# 3_3VBuckConverterSM.net
KiCad netlist of a schematic drawn in Altium Designer
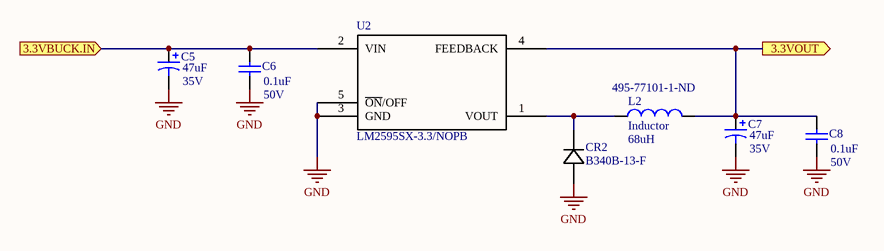
[diagram p0: 3.3VBuckConverterSM.SchDoc]

(export (version "E")
  (design (tool "Eeschema 10.0.6"))
  (components
    (comp (ref "C5")
      (value "47uF")
      (footprint "RB7.6-15")
      (description "Polarized Capacitor (Radial)")
      (fields
        (field (name "VOLTAGE RATING") "35V")
        (field (name "Comment") "Cap Pol1")
        (field (name "PUBLISHER") "Altium Limited")
      )
      (libsource (lib "Miscellaneous Devices") (part "Cap Pol1"))
    )
    (comp (ref "C6")
      (value "0.1uF")
      (footprint "RAD-0.3")
      (description "Capacitor")
      (fields
        (field (name "VOLTAGE RATING") "50V")
        (field (name "Comment") "Cap")
        (field (name "PUBLISHER") "Altium Limited")
      )
      (libsource (lib "Miscellaneous Devices") (part "Cap"))
    )
    (comp (ref "C7")
      (value "47uF")
      (footprint "RB7.6-15")
      (description "Polarized Capacitor (Radial)")
      (fields
        (field (name "VOLTAGE RATING") "35V")
        (field (name "Comment") "Cap Pol1")
        (field (name "PUBLISHER") "Altium Limited")
      )
      (libsource (lib "Miscellaneous Devices") (part "Cap Pol1"))
    )
    (comp (ref "C8")
      (value "0.1uF")
      (footprint "RAD-0.3")
      (description "Capacitor")
      (fields
        (field (name "VOLTAGE RATING") "50V")
        (field (name "Comment") "Cap")
        (field (name "PUBLISHER") "Altium Limited")
      )
      (libsource (lib "Miscellaneous Devices") (part "Cap"))
    )
    (comp (ref "CR2")
      (value "B340B-13-F")
      (footprint "B340A-13-F")
      (description "No Description Available")
      (fields (field (name "COPYRIGHT") "Copyright (C) 2022 Ultra Librarian. All rights reserved."))
      (libsource (lib "B340B-13-F") (part "B340B-13-F"))
    )
    (comp (ref "L2")
      (value "Inductor")
      (footprint "B82472P6683M000")
      (description "Ind Power Shielded Wirewound 68uH 20% 100KHz Ferrite 820mA Blister T/R")
      (fields
        (field (name "ALTIUM_VALUE") "68uH")
        (field (name "SUPPLIER PART NUMBER 1") "495-77101-1-ND")
        (field (name "MANUFACTURER") "TDK EPCOS")
        (field (name "MANUFACTURER PART NUMBER") "B82472P6683M000")
        (field (name "PUBLISHER") "Altium Limited")
      )
      (libsource (lib "Miscellaneous Devices") (part "Inductor"))
    )
    (comp (ref "U2")
      (value "LM2595SX-3.3/NOPB")
      (footprint "LM2595SX-3P3")
      (libsource (lib "Parts") (part "LM2595SX-3.3/NOPB"))
    )
  )
  (nets
    (net (code "1") (name "/3.3VBUCK.IN") (class "Default")
      (node (ref "C5") (pin "1") (pinfunction "1_1") (pintype "passive"))
      (node (ref "C6") (pin "2") (pinfunction "2_2") (pintype "passive"))
      (node (ref "U2") (pin "2") (pinfunction "VIN_2") (pintype "passive"))
    )
    (net (code "2") (name "/3.3VOUT") (class "Default")
      (node (ref "C7") (pin "1") (pinfunction "1_1") (pintype "passive"))
      (node (ref "C8") (pin "2") (pinfunction "2_2") (pintype "passive"))
      (node (ref "L2") (pin "2") (pinfunction "2_2") (pintype "passive"))
      (node (ref "U2") (pin "4") (pinfunction "FEEDBACK_4") (pintype "passive"))
    )
    (net (code "3") (name "GND") (class "Default")
      (node (ref "C5") (pin "2") (pinfunction "2_2") (pintype "passive"))
      (node (ref "C6") (pin "1") (pinfunction "1_1") (pintype "passive"))
      (node (ref "C7") (pin "2") (pinfunction "2_2") (pintype "passive"))
      (node (ref "C8") (pin "1") (pinfunction "1_1") (pintype "passive"))
      (node (ref "CR2") (pin "2") (pinfunction "2_2") (pintype "passive"))
      (node (ref "U2") (pin "3") (pinfunction "GND_3") (pintype "passive"))
      (node (ref "U2") (pin "5") (pinfunction "~{ON}/OFF_5") (pintype "passive"))
    )
    (net (code "4") (name "Net-(U2-VOUT)") (class "Default")
      (node (ref "CR2") (pin "1") (pinfunction "1_1") (pintype "passive"))
      (node (ref "L2") (pin "1") (pinfunction "1_1") (pintype "passive"))
      (node (ref "U2") (pin "1") (pinfunction "VOUT_1") (pintype "passive"))
    )
  )
)
